# SHR_TM3.net
KiCad netlist of a schematic drawn in Altium Designer
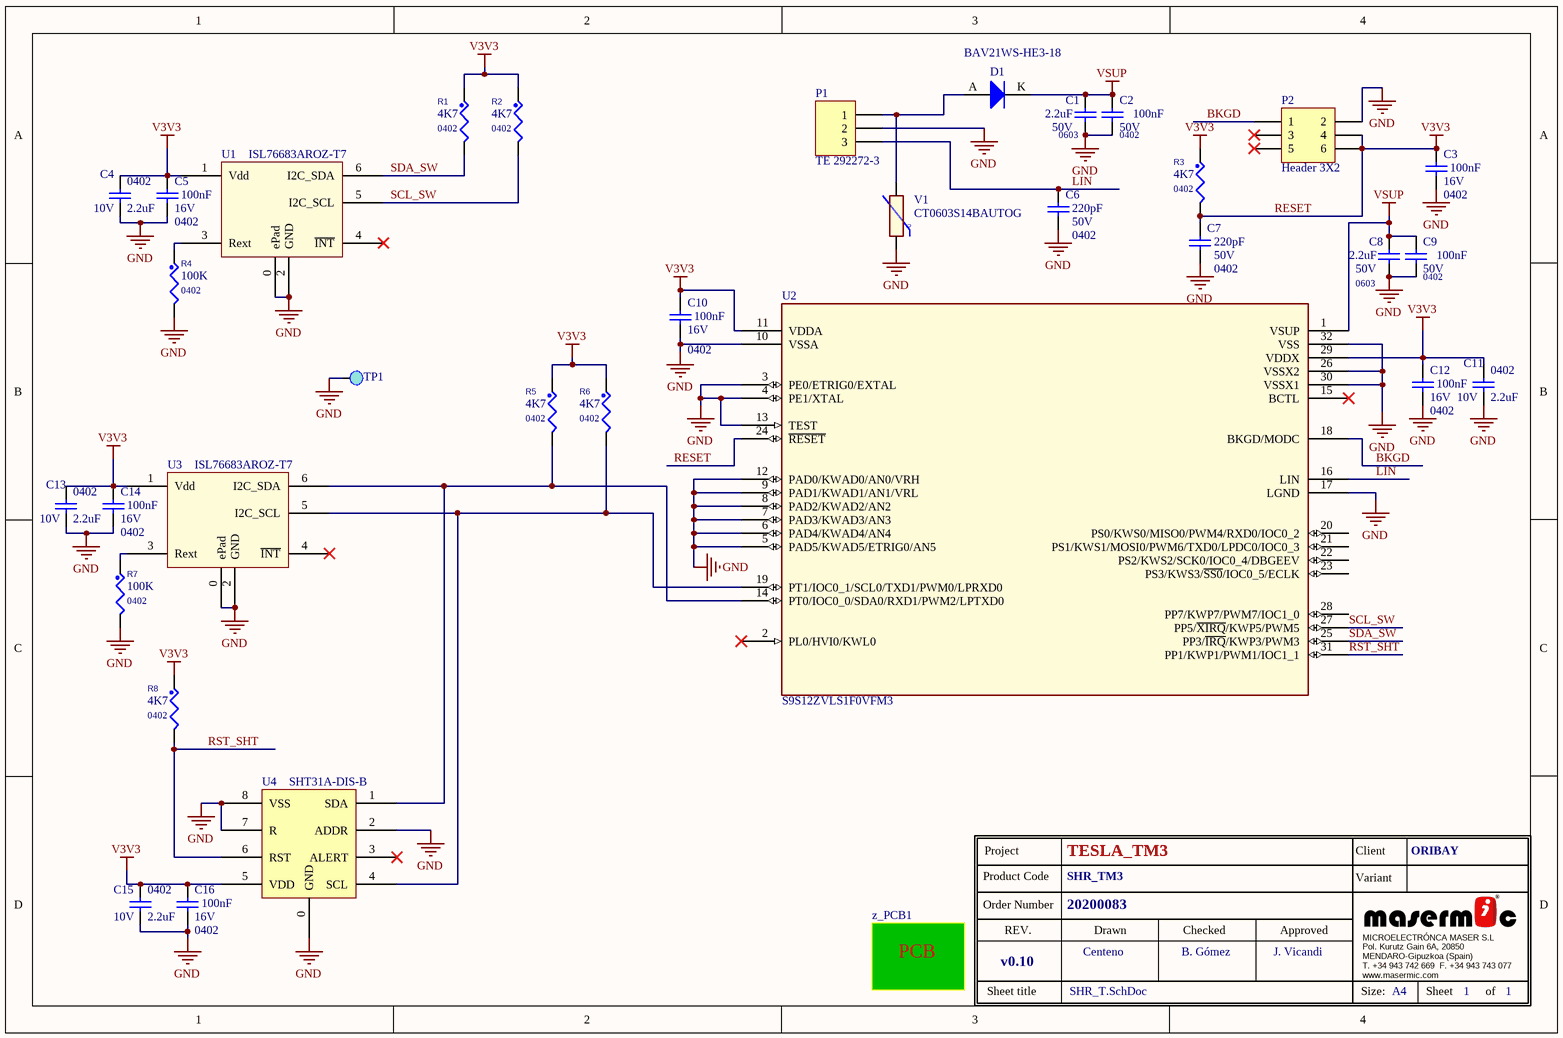
[diagram p0: SHR_TM3.SchDoc]

(export (version "E")
  (design (tool "Eeschema 10.0.6"))
  (components
    (comp (ref "C1")
      (value "2.2uF")
      (footprint "0603_CAP")
      (description "AEC Condensador")
      (fields
        (field (name "PACKAGE") "0603")
        (field (name "VOLTAGE") "50V")
        (field (name "TOLERANCE") "10%")
        (field (name "Comment") "Capacitor")
      )
      (libsource (lib "Miscellaneous Devices") (part "Cap Semi"))
    )
    (comp (ref "C2")
      (value "100nF")
      (footprint "0603_CAP")
      (description "AEC Flexiterm")
      (fields
        (field (name "PACKAGE") "0402")
        (field (name "VOLTAGE") "50V")
        (field (name "TOLERANCE") "10%")
        (field (name "Comment") "Capacitor")
      )
      (libsource (lib "Miscellaneous Devices") (part "Cap Semi"))
    )
    (comp (ref "C3")
      (value "100nF")
      (footprint "0402_CAP")
      (description "AEC Condensador")
      (fields
        (field (name "PACKAGE") "0402")
        (field (name "VOLTAGE") "16V")
        (field (name "TOLERANCE") "10%")
        (field (name "Comment") "Capacitor")
      )
      (libsource (lib "Miscellaneous Devices") (part "Cap Semi"))
    )
    (comp (ref "C4")
      (value "2.2uF")
      (footprint "0402_CAP")
      (description "AEC Condensador")
      (fields
        (field (name "PACKAGE") "0402")
        (field (name "VOLTAGE") "10V")
        (field (name "TOLERANCE") "10%")
        (field (name "Comment") "Capacitor")
      )
      (libsource (lib "Miscellaneous Devices") (part "Cap Semi"))
    )
    (comp (ref "C5")
      (value "100nF")
      (footprint "0402_CAP")
      (description "AEC Condensador")
      (fields
        (field (name "PACKAGE") "0402")
        (field (name "VOLTAGE") "16V")
        (field (name "TOLERANCE") "10%")
        (field (name "Comment") "Capacitor")
      )
      (libsource (lib "Miscellaneous Devices") (part "Cap Semi"))
    )
    (comp (ref "C6")
      (value "220pF")
      (footprint "0402_CAP")
      (description "AEC Condensador")
      (fields
        (field (name "PACKAGE") "0402")
        (field (name "VOLTAGE") "50V")
        (field (name "TOLERANCE") "15%")
        (field (name "Comment") "Capacitor")
      )
      (libsource (lib "MICROM_FASE_II") (part "Cap"))
    )
    (comp (ref "C7")
      (value "220pF")
      (footprint "0402_CAP")
      (description "AEC Condensador")
      (fields
        (field (name "PACKAGE") "0402")
        (field (name "VOLTAGE") "50V")
        (field (name "TOLERANCE") "15%")
        (field (name "Comment") "Capacitor")
      )
      (libsource (lib "MICROM_FASE_II") (part "Cap"))
    )
    (comp (ref "C8")
      (value "2.2uF")
      (footprint "0603_CAP")
      (description "AEC Condensador")
      (fields
        (field (name "PACKAGE") "0603")
        (field (name "VOLTAGE") "50V")
        (field (name "TOLERANCE") "10%")
        (field (name "Comment") "Capacitor")
      )
      (libsource (lib "Miscellaneous Devices") (part "Cap Semi"))
    )
    (comp (ref "C9")
      (value "100nF")
      (footprint "0603_CAP")
      (description "AEC Flexiterm")
      (fields
        (field (name "PACKAGE") "0402")
        (field (name "VOLTAGE") "50V")
        (field (name "TOLERANCE") "10%")
        (field (name "Comment") "Capacitor")
      )
      (libsource (lib "Miscellaneous Devices") (part "Cap Semi"))
    )
    (comp (ref "C10")
      (value "100nF")
      (footprint "0402_CAP")
      (description "AEC Condensador")
      (fields
        (field (name "PACKAGE") "0402")
        (field (name "VOLTAGE") "16V")
        (field (name "TOLERANCE") "10%")
        (field (name "Comment") "Capacitor")
      )
      (libsource (lib "Miscellaneous Devices") (part "Cap Semi"))
    )
    (comp (ref "C11")
      (value "2.2uF")
      (footprint "0402_CAP")
      (description "AEC Condensador")
      (fields
        (field (name "PACKAGE") "0402")
        (field (name "VOLTAGE") "10V")
        (field (name "TOLERANCE") "10%")
        (field (name "Comment") "Capacitor")
      )
      (libsource (lib "Miscellaneous Devices") (part "Cap Semi"))
    )
    (comp (ref "C12")
      (value "100nF")
      (footprint "0402_CAP")
      (description "AEC Condensador")
      (fields
        (field (name "PACKAGE") "0402")
        (field (name "VOLTAGE") "16V")
        (field (name "TOLERANCE") "10%")
        (field (name "Comment") "Capacitor")
      )
      (libsource (lib "Miscellaneous Devices") (part "Cap Semi"))
    )
    (comp (ref "C13")
      (value "2.2uF")
      (footprint "0402_CAP")
      (description "AEC Condensador")
      (fields
        (field (name "PACKAGE") "0402")
        (field (name "VOLTAGE") "10V")
        (field (name "TOLERANCE") "10%")
        (field (name "Comment") "Capacitor")
      )
      (libsource (lib "Miscellaneous Devices") (part "Cap Semi"))
    )
    (comp (ref "C14")
      (value "100nF")
      (footprint "0402_CAP")
      (description "AEC Condensador")
      (fields
        (field (name "PACKAGE") "0402")
        (field (name "VOLTAGE") "16V")
        (field (name "TOLERANCE") "10%")
        (field (name "Comment") "Capacitor")
      )
      (libsource (lib "Miscellaneous Devices") (part "Cap Semi"))
    )
    (comp (ref "C15")
      (value "2.2uF")
      (footprint "0402_CAP")
      (description "AEC Condensador")
      (fields
        (field (name "PACKAGE") "0402")
        (field (name "VOLTAGE") "10V")
        (field (name "TOLERANCE") "10%")
        (field (name "Comment") "Capacitor")
      )
      (libsource (lib "Miscellaneous Devices") (part "Cap Semi"))
    )
    (comp (ref "C16")
      (value "100nF")
      (footprint "0402_CAP")
      (description "AEC Condensador")
      (fields
        (field (name "PACKAGE") "0402")
        (field (name "VOLTAGE") "16V")
        (field (name "TOLERANCE") "10%")
        (field (name "Comment") "Capacitor")
      )
      (libsource (lib "Miscellaneous Devices") (part "Cap Semi"))
    )
    (comp (ref "D1")
      (value "Diode")
      (footprint "SOD323 (REFLOW-DIODE_V2) NXP")
      (description "AEC Diodo")
      (fields (field (name "COD. FAB") "BAV21WS-HE3-18") (field (name "VOLTAGE") "200V"))
      (libsource (lib "Miscellaneous Devices") (part "Diode"))
    )
    (comp (ref "P1")
      (value "TE 292272-3")
      (footprint "CON_TH_3P_1.27mm")
      (libsource (lib "Miscellaneous Connectors") (part "Header 3"))
    )
    (comp (ref "P2")
      (value "Header 3X2")
      (footprint "HDR2X3")
      (description "Header, 3-Pin, Dual row")
      (fields (field (name "PUBLISHER") "Altium Limited"))
      (libsource (lib "Miscellaneous Connectors") (part "Header 3X2"))
    )
    (comp (ref "R1")
      (value "4K7")
      (footprint "0402_RES")
      (description "AEC")
      (fields (field (name "POWER") "1/16w") (field (name "PACKAGE") "0402") (field (name "TOLERANCE") "1%"))
      (libsource (lib "MICROM_FASE_II") (part "RES_Dup2"))
    )
    (comp (ref "R2")
      (value "4K7")
      (footprint "0402_RES")
      (description "AEC")
      (fields (field (name "POWER") "1/16w") (field (name "PACKAGE") "0402") (field (name "TOLERANCE") "1%"))
      (libsource (lib "MICROM_FASE_II") (part "RES_Dup2"))
    )
    (comp (ref "R3")
      (value "4K7")
      (footprint "0402_RES")
      (description "AEC")
      (fields (field (name "POWER") "1/16w") (field (name "PACKAGE") "0402") (field (name "TOLERANCE") "1%"))
      (libsource (lib "MICROM_FASE_II") (part "RES_Dup2"))
    )
    (comp (ref "R4")
      (value "100K")
      (footprint "0402_RES")
      (description "AEC")
      (fields (field (name "POWER") "1/16W") (field (name "PACKAGE") "0402") (field (name "TOLERANCE") "1%"))
      (libsource (lib "MICROM_FASE_II") (part "RES_Dup2"))
    )
    (comp (ref "R5")
      (value "4K7")
      (footprint "0402_RES")
      (description "AEC")
      (fields (field (name "POWER") "1/16w") (field (name "PACKAGE") "0402") (field (name "TOLERANCE") "1%"))
      (libsource (lib "MICROM_FASE_II") (part "RES_Dup2"))
    )
    (comp (ref "R6")
      (value "4K7")
      (footprint "0402_RES")
      (description "AEC")
      (fields (field (name "POWER") "1/16w") (field (name "PACKAGE") "0402") (field (name "TOLERANCE") "1%"))
      (libsource (lib "MICROM_FASE_II") (part "RES_Dup2"))
    )
    (comp (ref "R7")
      (value "100K")
      (footprint "0402_RES")
      (description "AEC")
      (fields (field (name "POWER") "1/16W") (field (name "PACKAGE") "0402") (field (name "TOLERANCE") "1%"))
      (libsource (lib "MICROM_FASE_II") (part "RES_Dup2"))
    )
    (comp (ref "R8")
      (value "4K7")
      (footprint "0402_RES")
      (description "AEC")
      (fields (field (name "POWER") "1/16w") (field (name "PACKAGE") "0402") (field (name "TOLERANCE") "1%"))
      (libsource (lib "MICROM_FASE_II") (part "RES_Dup2"))
    )
    (comp (ref "TP1")
      (value "TP de Produccion")
      (footprint "TP_0.5")
      (libsource (lib "BaseNEW") (part "TP de Produccion"))
    )
    (comp (ref "U1")
      (value "Sensor de luminosidad")
      (footprint "ODFN 6 Ld (2.1x2mm)")
      (description "AEC-Q100")
      (fields (field (name "VOLTAGE") "3V3") (field (name "COD. FAB") "ISL76683AROZ-T7"))
      (libsource (lib "BaseNEW") (part "ISL76683"))
    )
    (comp (ref "U2")
      (value "S9S12ZVLS1F0VFM3")
      (footprint "HVQFN-32")
      (libsource (lib "SCH-29227_Library") (part "S9S12ZVLS1F0VFM3"))
    )
    (comp (ref "U3")
      (value "Sensor de luminosidad")
      (footprint "ODFN 6 Ld (2.1x2mm)")
      (description "AEC-Q100")
      (fields (field (name "VOLTAGE") "3V3") (field (name "COD. FAB") "ISL76683AROZ-T7"))
      (libsource (lib "BaseNEW") (part "ISL76683"))
    )
    (comp (ref "U4")
      (value "SHT31-DIS-B")
      (footprint "DFN8 (SHT31-DIS-B)")
      (description "Sensor de humedad")
      (fields (field (name "COD. FAB") "SHT31A-DIS-B"))
      (libsource (lib "55SHR_CONA") (part "SHT31-DIS-B"))
    )
    (comp (ref "V1")
      (value "CT0603S14BAUTOG")
      (footprint "0603_CAP")
      (libsource (lib "SIOV") (part "CN2220K30AUTOG"))
    )
    (comp (ref "z_PCB1") (value "~") (libsource (lib "GAIKER_1") (part "PCB")))
  )
  (nets
    (net (code "1") (name "/BKGD") (class "Default")
      (node (ref "P2") (pin "1") (pinfunction "1_1") (pintype "passive"))
      (node (ref "U2") (pin "18") (pinfunction "BKGD/MODC_18") (pintype "passive"))
    )
    (net (code "2") (name "/LIN") (class "Default")
      (node (ref "C6") (pin "2") (pinfunction "2_2") (pintype "passive"))
      (node (ref "P1") (pin "3") (pinfunction "3_3") (pintype "passive"))
      (node (ref "U2") (pin "16") (pinfunction "LIN_16") (pintype "passive"))
    )
    (net (code "3") (name "/RST_SHT") (class "Default")
      (node (ref "R8") (pin "2") (pinfunction "2_2") (pintype "passive"))
      (node (ref "U2") (pin "31") (pinfunction "PP1/KWP1/PWM1/IOC1_1_31") (pintype "bidirectional"))
      (node (ref "U4") (pin "6") (pinfunction "RST_6") (pintype "passive"))
    )
    (net (code "4") (name "/SCL_SW") (class "Default")
      (node (ref "R2") (pin "2") (pinfunction "2_2") (pintype "passive"))
      (node (ref "U1") (pin "5") (pinfunction "I2C_SCL_5") (pintype "passive"))
      (node (ref "U2") (pin "27") (pinfunction "PP5/~{XIRQ}/KWP5/PWM5_27") (pintype "bidirectional"))
    )
    (net (code "5") (name "/SDA_SW") (class "Default")
      (node (ref "R1") (pin "2") (pinfunction "2_2") (pintype "passive"))
      (node (ref "U1") (pin "6") (pinfunction "I2C_SDA_6") (pintype "passive"))
      (node (ref "U2") (pin "25") (pinfunction "PP3/~{IRQ}/KWP3/PWM3_25") (pintype "bidirectional"))
    )
    (net (code "6") (name "GND") (class "Default")
      (node (ref "C1") (pin "1") (pinfunction "1_1") (pintype "passive"))
      (node (ref "C10") (pin "1") (pinfunction "1_1") (pintype "passive"))
      (node (ref "C11") (pin "1") (pinfunction "1_1") (pintype "passive"))
      (node (ref "C12") (pin "1") (pinfunction "1_1") (pintype "passive"))
      (node (ref "C13") (pin "1") (pinfunction "1_1") (pintype "passive"))
      (node (ref "C14") (pin "1") (pinfunction "1_1") (pintype "passive"))
      (node (ref "C15") (pin "1") (pinfunction "1_1") (pintype "passive"))
      (node (ref "C16") (pin "1") (pinfunction "1_1") (pintype "passive"))
      (node (ref "C2") (pin "1") (pinfunction "1_1") (pintype "passive"))
      (node (ref "C3") (pin "1") (pinfunction "1_1") (pintype "passive"))
      (node (ref "C4") (pin "1") (pinfunction "1_1") (pintype "passive"))
      (node (ref "C5") (pin "1") (pinfunction "1_1") (pintype "passive"))
      (node (ref "C6") (pin "1") (pinfunction "1_1") (pintype "passive"))
      (node (ref "C7") (pin "1") (pinfunction "1_1") (pintype "passive"))
      (node (ref "C8") (pin "1") (pinfunction "1_1") (pintype "passive"))
      (node (ref "C9") (pin "1") (pinfunction "1_1") (pintype "passive"))
      (node (ref "P1") (pin "2") (pinfunction "2_2") (pintype "passive"))
      (node (ref "P2") (pin "2") (pinfunction "2_2") (pintype "passive"))
      (node (ref "R4") (pin "2") (pinfunction "2_2") (pintype "passive"))
      (node (ref "R7") (pin "2") (pinfunction "2_2") (pintype "passive"))
      (node (ref "TP1") (pin "0") (pinfunction "0_0") (pintype "passive"))
      (node (ref "U1") (pin "0") (pinfunction "ePad_0") (pintype "passive"))
      (node (ref "U1") (pin "2") (pinfunction "GND_2") (pintype "passive"))
      (node (ref "U2") (pin "10") (pinfunction "VSSA_10") (pintype "power_in"))
      (node (ref "U2") (pin "12") (pinfunction "PAD0/KWAD0/AN0/VRH_12") (pintype "bidirectional"))
      (node (ref "U2") (pin "13") (pinfunction "TEST_13") (pintype "input"))
      (node (ref "U2") (pin "17") (pinfunction "LGND_17") (pintype "power_in"))
      (node (ref "U2") (pin "26") (pinfunction "VSSX2_26") (pintype "power_in"))
      (node (ref "U2") (pin "3") (pinfunction "PE0/ETRIG0/EXTAL_3") (pintype "bidirectional"))
      (node (ref "U2") (pin "30") (pinfunction "VSSX1_30") (pintype "power_in"))
      (node (ref "U2") (pin "32") (pinfunction "VSS_32") (pintype "power_in"))
      (node (ref "U2") (pin "4") (pinfunction "PE1/XTAL_4") (pintype "bidirectional"))
      (node (ref "U2") (pin "5") (pinfunction "PAD5/KWAD5/ETRIG0/AN5_5") (pintype "bidirectional"))
      (node (ref "U2") (pin "6") (pinfunction "PAD4/KWAD4/AN4_6") (pintype "bidirectional"))
      (node (ref "U2") (pin "7") (pinfunction "PAD3/KWAD3/AN3_7") (pintype "bidirectional"))
      (node (ref "U2") (pin "8") (pinfunction "PAD2/KWAD2/AN2_8") (pintype "bidirectional"))
      (node (ref "U2") (pin "9") (pinfunction "PAD1/KWAD1/AN1/VRL_9") (pintype "bidirectional"))
      (node (ref "U3") (pin "0") (pinfunction "ePad_0") (pintype "passive"))
      (node (ref "U3") (pin "2") (pinfunction "GND_2") (pintype "passive"))
      (node (ref "U4") (pin "0") (pinfunction "GND_0") (pintype "passive"))
      (node (ref "U4") (pin "2") (pinfunction "ADDR_2") (pintype "passive"))
      (node (ref "U4") (pin "7") (pinfunction "R_7") (pintype "passive"))
      (node (ref "U4") (pin "8") (pinfunction "VSS_8") (pintype "passive"))
      (node (ref "V1") (pin "1") (pinfunction "1_1") (pintype "passive"))
    )
    (net (code "7") (name "Net-(D1-PadA)") (class "Default")
      (node (ref "D1") (pin "A") (pinfunction "A_A") (pintype "passive"))
      (node (ref "P1") (pin "1") (pinfunction "1_1") (pintype "passive"))
      (node (ref "V1") (pin "2") (pinfunction "2_2") (pintype "passive"))
    )
    (net (code "8") (name "Net-(U1-Rext)") (class "Default")
      (node (ref "R4") (pin "1") (pinfunction "1_1") (pintype "passive"))
      (node (ref "U1") (pin "3") (pinfunction "Rext_3") (pintype "passive"))
    )
    (net (code "9") (name "Net-(U2-PT0{slash}IOC0_0{slash}SDA0{slash}RXD1{slash}PWM2{slash}LPTXD0)") (class "Default")
      (node (ref "R5") (pin "2") (pinfunction "2_2") (pintype "passive"))
      (node (ref "U2") (pin "14") (pinfunction "PT0/IOC0_0/SDA0/RXD1/PWM2/LPTXD0_14") (pintype "bidirectional"))
      (node (ref "U3") (pin "6") (pinfunction "I2C_SDA_6") (pintype "passive"))
      (node (ref "U4") (pin "1") (pinfunction "SDA_1") (pintype "passive"))
    )
    (net (code "10") (name "Net-(U2-PT1{slash}IOC0_1{slash}SCL0{slash}TXD1{slash}PWM0{slash}LPRXD0)") (class "Default")
      (node (ref "R6") (pin "2") (pinfunction "2_2") (pintype "passive"))
      (node (ref "U2") (pin "19") (pinfunction "PT1/IOC0_1/SCL0/TXD1/PWM0/LPRXD0_19") (pintype "bidirectional"))
      (node (ref "U3") (pin "5") (pinfunction "I2C_SCL_5") (pintype "passive"))
      (node (ref "U4") (pin "4") (pinfunction "SCL_4") (pintype "passive"))
    )
    (net (code "11") (name "Net-(U3-Rext)") (class "Default")
      (node (ref "R7") (pin "1") (pinfunction "1_1") (pintype "passive"))
      (node (ref "U3") (pin "3") (pinfunction "Rext_3") (pintype "passive"))
    )
    (net (code "12") (name "V3V3") (class "Default")
      (node (ref "C10") (pin "2") (pinfunction "2_2") (pintype "passive"))
      (node (ref "C11") (pin "2") (pinfunction "2_2") (pintype "passive"))
      (node (ref "C12") (pin "2") (pinfunction "2_2") (pintype "passive"))
      (node (ref "C13") (pin "2") (pinfunction "2_2") (pintype "passive"))
      (node (ref "C14") (pin "2") (pinfunction "2_2") (pintype "passive"))
      (node (ref "C15") (pin "2") (pinfunction "2_2") (pintype "passive"))
      (node (ref "C16") (pin "2") (pinfunction "2_2") (pintype "passive"))
      (node (ref "C3") (pin "2") (pinfunction "2_2") (pintype "passive"))
      (node (ref "C4") (pin "2") (pinfunction "2_2") (pintype "passive"))
      (node (ref "C5") (pin "2") (pinfunction "2_2") (pintype "passive"))
      (node (ref "C7") (pin "2") (pinfunction "2_2") (pintype "passive"))
      (node (ref "P2") (pin "4") (pinfunction "4_4") (pintype "passive"))
      (node (ref "P2") (pin "6") (pinfunction "6_6") (pintype "passive"))
      (node (ref "R1") (pin "1") (pinfunction "1_1") (pintype "passive"))
      (node (ref "R2") (pin "1") (pinfunction "1_1") (pintype "passive"))
      (node (ref "R3") (pin "1") (pinfunction "1_1") (pintype "passive"))
      (node (ref "R3") (pin "2") (pinfunction "2_2") (pintype "passive"))
      (node (ref "R5") (pin "1") (pinfunction "1_1") (pintype "passive"))
      (node (ref "R6") (pin "1") (pinfunction "1_1") (pintype "passive"))
      (node (ref "R8") (pin "1") (pinfunction "1_1") (pintype "passive"))
      (node (ref "U1") (pin "1") (pinfunction "Vdd_1") (pintype "passive"))
      (node (ref "U2") (pin "11") (pinfunction "VDDA_11") (pintype "power_in"))
      (node (ref "U2") (pin "24") (pinfunction "~{RESET}_24") (pintype "bidirectional"))
      (node (ref "U2") (pin "29") (pinfunction "VDDX_29") (pintype "power_in"))
      (node (ref "U3") (pin "1") (pinfunction "Vdd_1") (pintype "passive"))
      (node (ref "U4") (pin "5") (pinfunction "VDD_5") (pintype "passive"))
    )
    (net (code "13") (name "VSUP") (class "Default")
      (node (ref "C1") (pin "2") (pinfunction "2_2") (pintype "passive"))
      (node (ref "C2") (pin "2") (pinfunction "2_2") (pintype "passive"))
      (node (ref "C8") (pin "2") (pinfunction "2_2") (pintype "passive"))
      (node (ref "C9") (pin "2") (pinfunction "2_2") (pintype "passive"))
      (node (ref "D1") (pin "K") (pinfunction "K_K") (pintype "passive"))
      (node (ref "U2") (pin "1") (pinfunction "VSUP_1") (pintype "power_in"))
    )
    (net (code "14") (name "unconnected-(P2-Pad3)") (class "Default")
      (node (ref "P2") (pin "3") (pinfunction "3_3") (pintype "passive+no_connect"))
    )
    (net (code "15") (name "unconnected-(P2-Pad5)") (class "Default")
      (node (ref "P2") (pin "5") (pinfunction "5_5") (pintype "passive+no_connect"))
    )
    (net (code "16") (name "unconnected-(U1-~{INT}-Pad4)") (class "Default")
      (node (ref "U1") (pin "4") (pinfunction "~{INT}_4") (pintype "passive+no_connect"))
    )
    (net (code "17") (name "unconnected-(U2-BCTL-Pad15)") (class "Default")
      (node (ref "U2") (pin "15") (pinfunction "BCTL_15") (pintype "passive+no_connect"))
    )
    (net (code "18") (name "unconnected-(U2-PL0{slash}HVI0{slash}KWL0-Pad2)") (class "Default")
      (node (ref "U2") (pin "2") (pinfunction "PL0/HVI0/KWL0_2") (pintype "input+no_connect"))
    )
    (net (code "19") (name "unconnected-(U2-PP7{slash}KWP7{slash}PWM7{slash}IOC1_0-Pad28)") (class "Default")
      (node (ref "U2") (pin "28") (pinfunction "PP7/KWP7/PWM7/IOC1_0_28") (pintype "bidirectional"))
    )
    (net (code "20") (name "unconnected-(U2-PS0{slash}KWS0{slash}MISO0{slash}PWM4{slash}RXD0{slash}IOC0_2-Pad20)") (class "Default")
      (node (ref "U2") (pin "20") (pinfunction "PS0/KWS0/MISO0/PWM4/RXD0/IOC0_2_20") (pintype "bidirectional"))
    )
    (net (code "21") (name "unconnected-(U2-PS1{slash}KWS1{slash}MOSI0{slash}PWM6{slash}TXD0{slash}LPDC0{slash}IOC0_3-Pad21)") (class "Default")
      (node (ref "U2") (pin "21") (pinfunction "PS1/KWS1/MOSI0/PWM6/TXD0/LPDC0/IOC0_3_21") (pintype "bidirectional"))
    )
    (net (code "22") (name "unconnected-(U2-PS2{slash}KWS2{slash}SCK0{slash}IOC0_4{slash}DBGEEV-Pad22)") (class "Default")
      (node (ref "U2") (pin "22") (pinfunction "PS2/KWS2/SCK0/IOC0_4/DBGEEV_22") (pintype "bidirectional"))
    )
    (net (code "23") (name "unconnected-(U2-PS3{slash}KWS3{slash}~{SS0}{slash}IOC0_5{slash}ECLK-Pad23)") (class "Default")
      (node (ref "U2") (pin "23") (pinfunction "PS3/KWS3/~{SS0}/IOC0_5/ECLK_23") (pintype "bidirectional"))
    )
    (net (code "24") (name "unconnected-(U3-~{INT}-Pad4)") (class "Default")
      (node (ref "U3") (pin "4") (pinfunction "~{INT}_4") (pintype "passive+no_connect"))
    )
    (net (code "25") (name "unconnected-(U4-ALERT-Pad3)") (class "Default")
      (node (ref "U4") (pin "3") (pinfunction "ALERT_3") (pintype "passive+no_connect"))
    )
  )
)
